# BOTS.net
KiCad netlist of a schematic drawn in Altium Designer
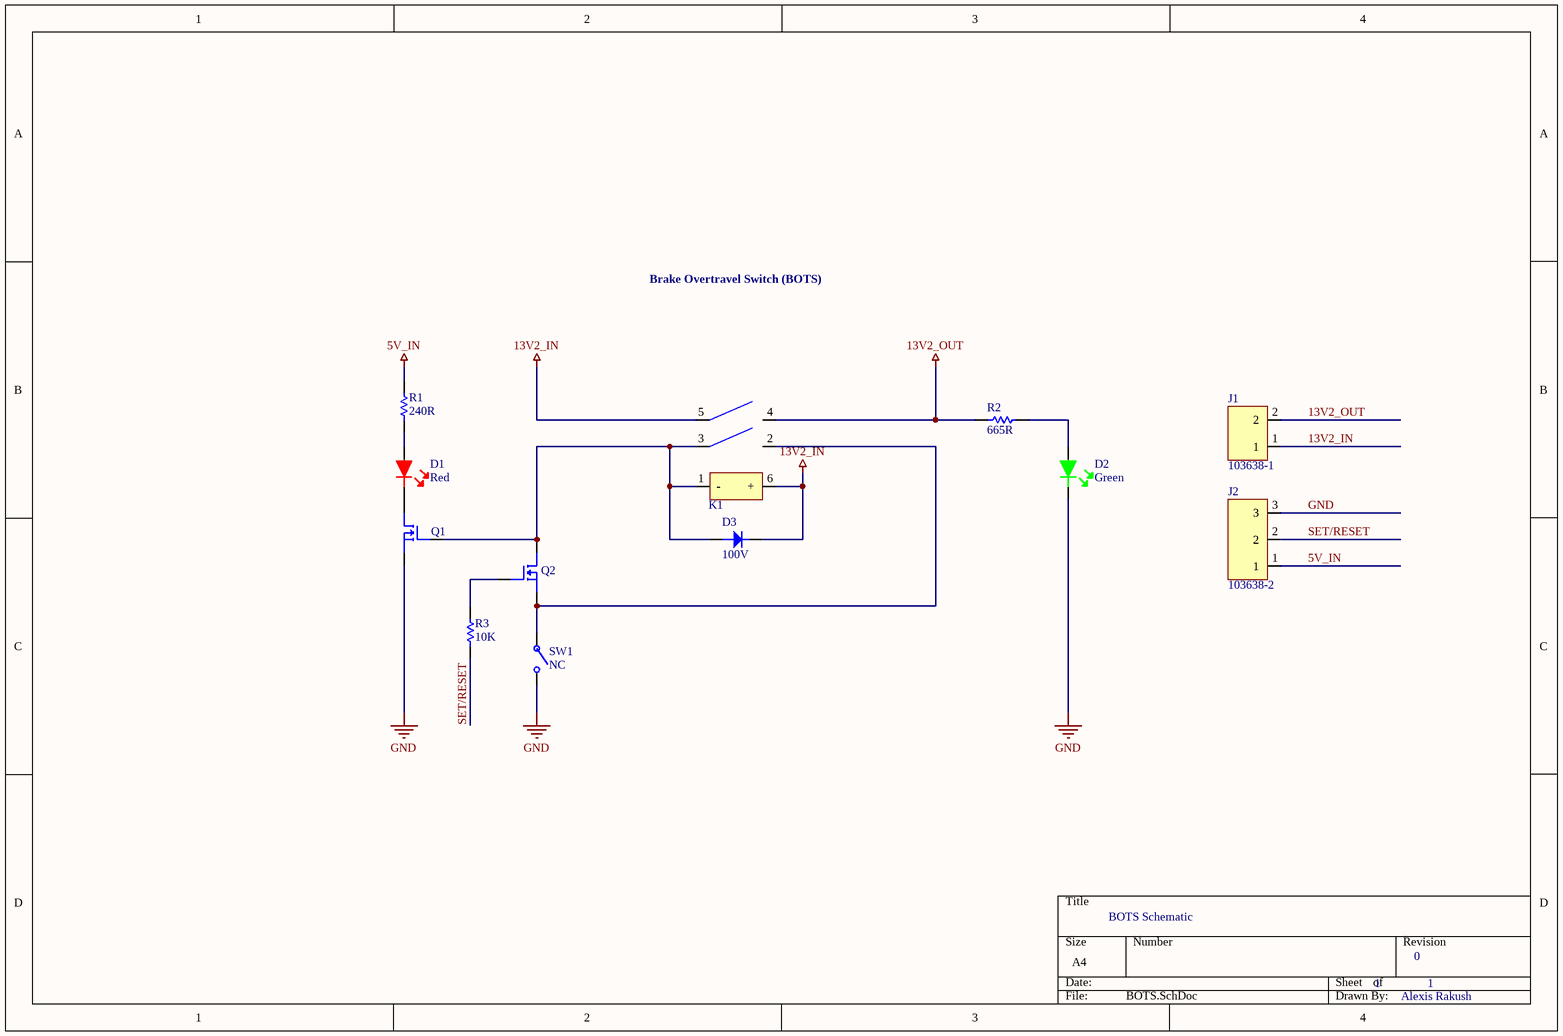
[diagram p0: BOTS.SchDoc]

(export (version "E")
  (design (tool "Eeschema 10.0.6"))
  (components
    (comp (ref "D1")
      (value "Red")
      (footprint "LED-0603")
      (description "LED RED CLEAR 0603 SMD")
      (fields
        (field (name "MANUFACTURER") "Wurth Electronics")
        (field (name "MANUFACTURER PART NUMBER") "150060RS75000")
      )
      (libsource (lib "LEDs") (part "LED-Red"))
    )
    (comp (ref "D2")
      (value "Green")
      (footprint "LED-0603")
      (description "LED GREEN CLEAR 0603 SMD")
      (fields
        (field (name "MANUFACTURER") "Wurth Electronics")
        (field (name "MANUFACTURER PART NUMBER") "150060VS75000")
      )
      (libsource (lib "LEDs") (part "LED-Green"))
    )
    (comp (ref "D3")
      (value "100V")
      (footprint "DO-214AA")
      (description "DIODE GEN PURP 100V 3A DO214AA")
      (fields (field (name "MANUFACTURER") "MCC") (field (name "MANUFACTURER PART NUMBER") "S3BB-TP"))
      (libsource (lib "Diodes") (part "Diode-100V-3A"))
    )
    (comp (ref "J1")
      (value "103638-1")
      (footprint "2PIN")
      (description "CONN HEADER VERT 2POS 2.54MM")
      (fields (field (name "MANUFACTURER") "TE Connectivity"))
      (libsource (lib "BOTS") (part "2PIN"))
    )
    (comp (ref "J2")
      (value "103638-2")
      (footprint "3PIN")
      (description "CONN HEADER VERT 3POS 2.54MM")
      (fields (field (name "MANUFACTURER") "TE Connectivity"))
      (libsource (lib "BOTS") (part "3PIN"))
    )
    (comp (ref "K1")
      (value "5-1419124-6")
      (footprint "RELAY DPST SDC")
      (description "General Purpose Relay, Osa Series, Power, Non Latching, Dpst-No, 12 Vdc, 3 A Rohs Compliant: Yes")
      (fields (field (name "MANUFACTURER") "TE Connectivity"))
      (libsource (lib "BOTS") (part "5-1419124-6"))
    )
    (comp (ref "Q1")
      (value "DMN6140L-13DICT-ND")
      (footprint "SOT-23-3")
      (description "MOSFET N-CH 60V 1.6A SOT23")
      (fields (field (name "MANUFACTURER") "Diodes") (field (name "MANUFACTURER PART NUMBER") "DMN6140L-13"))
      (libsource (lib "BOTS") (part "N-FET-60V-1.6A"))
    )
    (comp (ref "Q2")
      (value "DMN6140L-13DICT-ND")
      (footprint "SOT-23-3")
      (description "MOSFET N-CH 60V 1.6A SOT23")
      (fields (field (name "MANUFACTURER") "Diodes") (field (name "MANUFACTURER PART NUMBER") "DMN6140L-13"))
      (libsource (lib "BOTS") (part "N-FET-60V-1.6A"))
    )
    (comp (ref "R1")
      (value "240R")
      (footprint "RES-0402")
      (description "RES SMD 240 OHM 1% 1/10W 0402")
      (fields
        (field (name "MANUFACTURER") "Panasonic")
        (field (name "MANUFACTURER PART NUMBER") "ERJ-2RKF2400X")
      )
      (libsource (lib "Resistors") (part "0402-240R"))
    )
    (comp (ref "R2")
      (value "665R")
      (footprint "RES-0402")
      (description "RES SMD 665 OHM 1% 1/10W 0402")
      (fields
        (field (name "MANUFACTURER") "Panasonic")
        (field (name "MANUFACTURER PART NUMBER") "ERJ-2RKF6650X")
      )
      (libsource (lib "Resistors") (part "0402-665R"))
    )
    (comp (ref "R3")
      (value "10K")
      (footprint "RES-0603")
      (description "RES SMD 10K OHM 5% 1/10W 0603")
      (fields
        (field (name "MANUFACTURER") "Yageo")
        (field (name "MANUFACTURER PART NUMBER") "RC0603JR-0710KL")
      )
      (libsource (lib "BOTS") (part "0603-10KR"))
    )
    (comp (ref "SW1")
      (value "NC")
      (footprint "Switch")
      (description "SWITCH SNAP ACT SPST-NC 5A 125V")
      (fields (field (name "MANUFACTURER") "Omron") (field (name "MANUFACTURER PART NUMBER") "SS-5GL-F-2T"))
      (libsource (lib "BOTS") (part "Switch"))
    )
  )
  (nets
    (net (code "2") (name "/SET{slash}RESET") (class "Default")
      (node (ref "J2") (pin "2") (pinfunction "2_2") (pintype "passive"))
      (node (ref "R3") (pin "1") (pinfunction "1_1") (pintype "passive"))
    )
    (net (code "3") (name "5V_IN") (class "Default")
      (node (ref "J2") (pin "1") (pinfunction "1_1") (pintype "passive"))
      (node (ref "R1") (pin "2") (pinfunction "2_2") (pintype "passive"))
    )
    (net (code "4") (name "13V2_IN") (class "Default")
      (node (ref "D3") (pin "1") (pinfunction "1_1") (pintype "passive"))
      (node (ref "J1") (pin "1") (pinfunction "1_1") (pintype "passive"))
      (node (ref "K1") (pin "5") (pinfunction "5_5") (pintype "passive"))
      (node (ref "K1") (pin "6") (pinfunction "+_6") (pintype "passive"))
    )
    (net (code "5") (name "13V2_OUT") (class "Default")
      (node (ref "J1") (pin "2") (pinfunction "2_2") (pintype "passive"))
      (node (ref "K1") (pin "4") (pinfunction "4_4") (pintype "passive"))
      (node (ref "R2") (pin "1") (pinfunction "1_1") (pintype "passive"))
    )
    (net (code "6") (name "GND") (class "Default")
      (node (ref "D2") (pin "2") (pinfunction "2_2") (pintype "passive"))
      (node (ref "J2") (pin "3") (pinfunction "3_3") (pintype "passive"))
      (node (ref "Q1") (pin "3") (pinfunction "3_3") (pintype "passive"))
      (node (ref "SW1") (pin "2") (pinfunction "2_2") (pintype "passive"))
    )
    (net (code "7") (name "Net-(D1-Pad1)") (class "Default")
      (node (ref "D1") (pin "1") (pinfunction "1_1") (pintype "passive"))
      (node (ref "R1") (pin "1") (pinfunction "1_1") (pintype "passive"))
    )
    (net (code "8") (name "Net-(D1-Pad2)") (class "Default")
      (node (ref "D1") (pin "2") (pinfunction "2_2") (pintype "passive"))
      (node (ref "Q1") (pin "2") (pinfunction "2_2") (pintype "passive"))
    )
    (net (code "9") (name "Net-(D2-Pad1)") (class "Default")
      (node (ref "D2") (pin "1") (pinfunction "1_1") (pintype "passive"))
      (node (ref "R2") (pin "2") (pinfunction "2_2") (pintype "passive"))
    )
    (net (code "10") (name "Net-(K1--)") (class "Default")
      (node (ref "D3") (pin "2") (pinfunction "2_2") (pintype "passive"))
      (node (ref "K1") (pin "1") (pinfunction "-_1") (pintype "passive"))
      (node (ref "K1") (pin "3") (pinfunction "3_3") (pintype "passive"))
      (node (ref "Q1") (pin "1") (pinfunction "1_1") (pintype "passive"))
      (node (ref "Q2") (pin "2") (pinfunction "2_2") (pintype "passive"))
    )
    (net (code "11") (name "Net-(K1-Pad2)") (class "Default")
      (node (ref "K1") (pin "2") (pinfunction "2_2") (pintype "passive"))
      (node (ref "Q2") (pin "3") (pinfunction "3_3") (pintype "passive"))
      (node (ref "SW1") (pin "1") (pinfunction "1_1") (pintype "passive"))
    )
    (net (code "12") (name "Net-(Q2-Pad1)") (class "Default")
      (node (ref "Q2") (pin "1") (pinfunction "1_1") (pintype "passive"))
      (node (ref "R3") (pin "2") (pinfunction "2_2") (pintype "passive"))
    )
  )
)
